# Qiao.net
KiCad netlist of a schematic drawn in Altium Designer
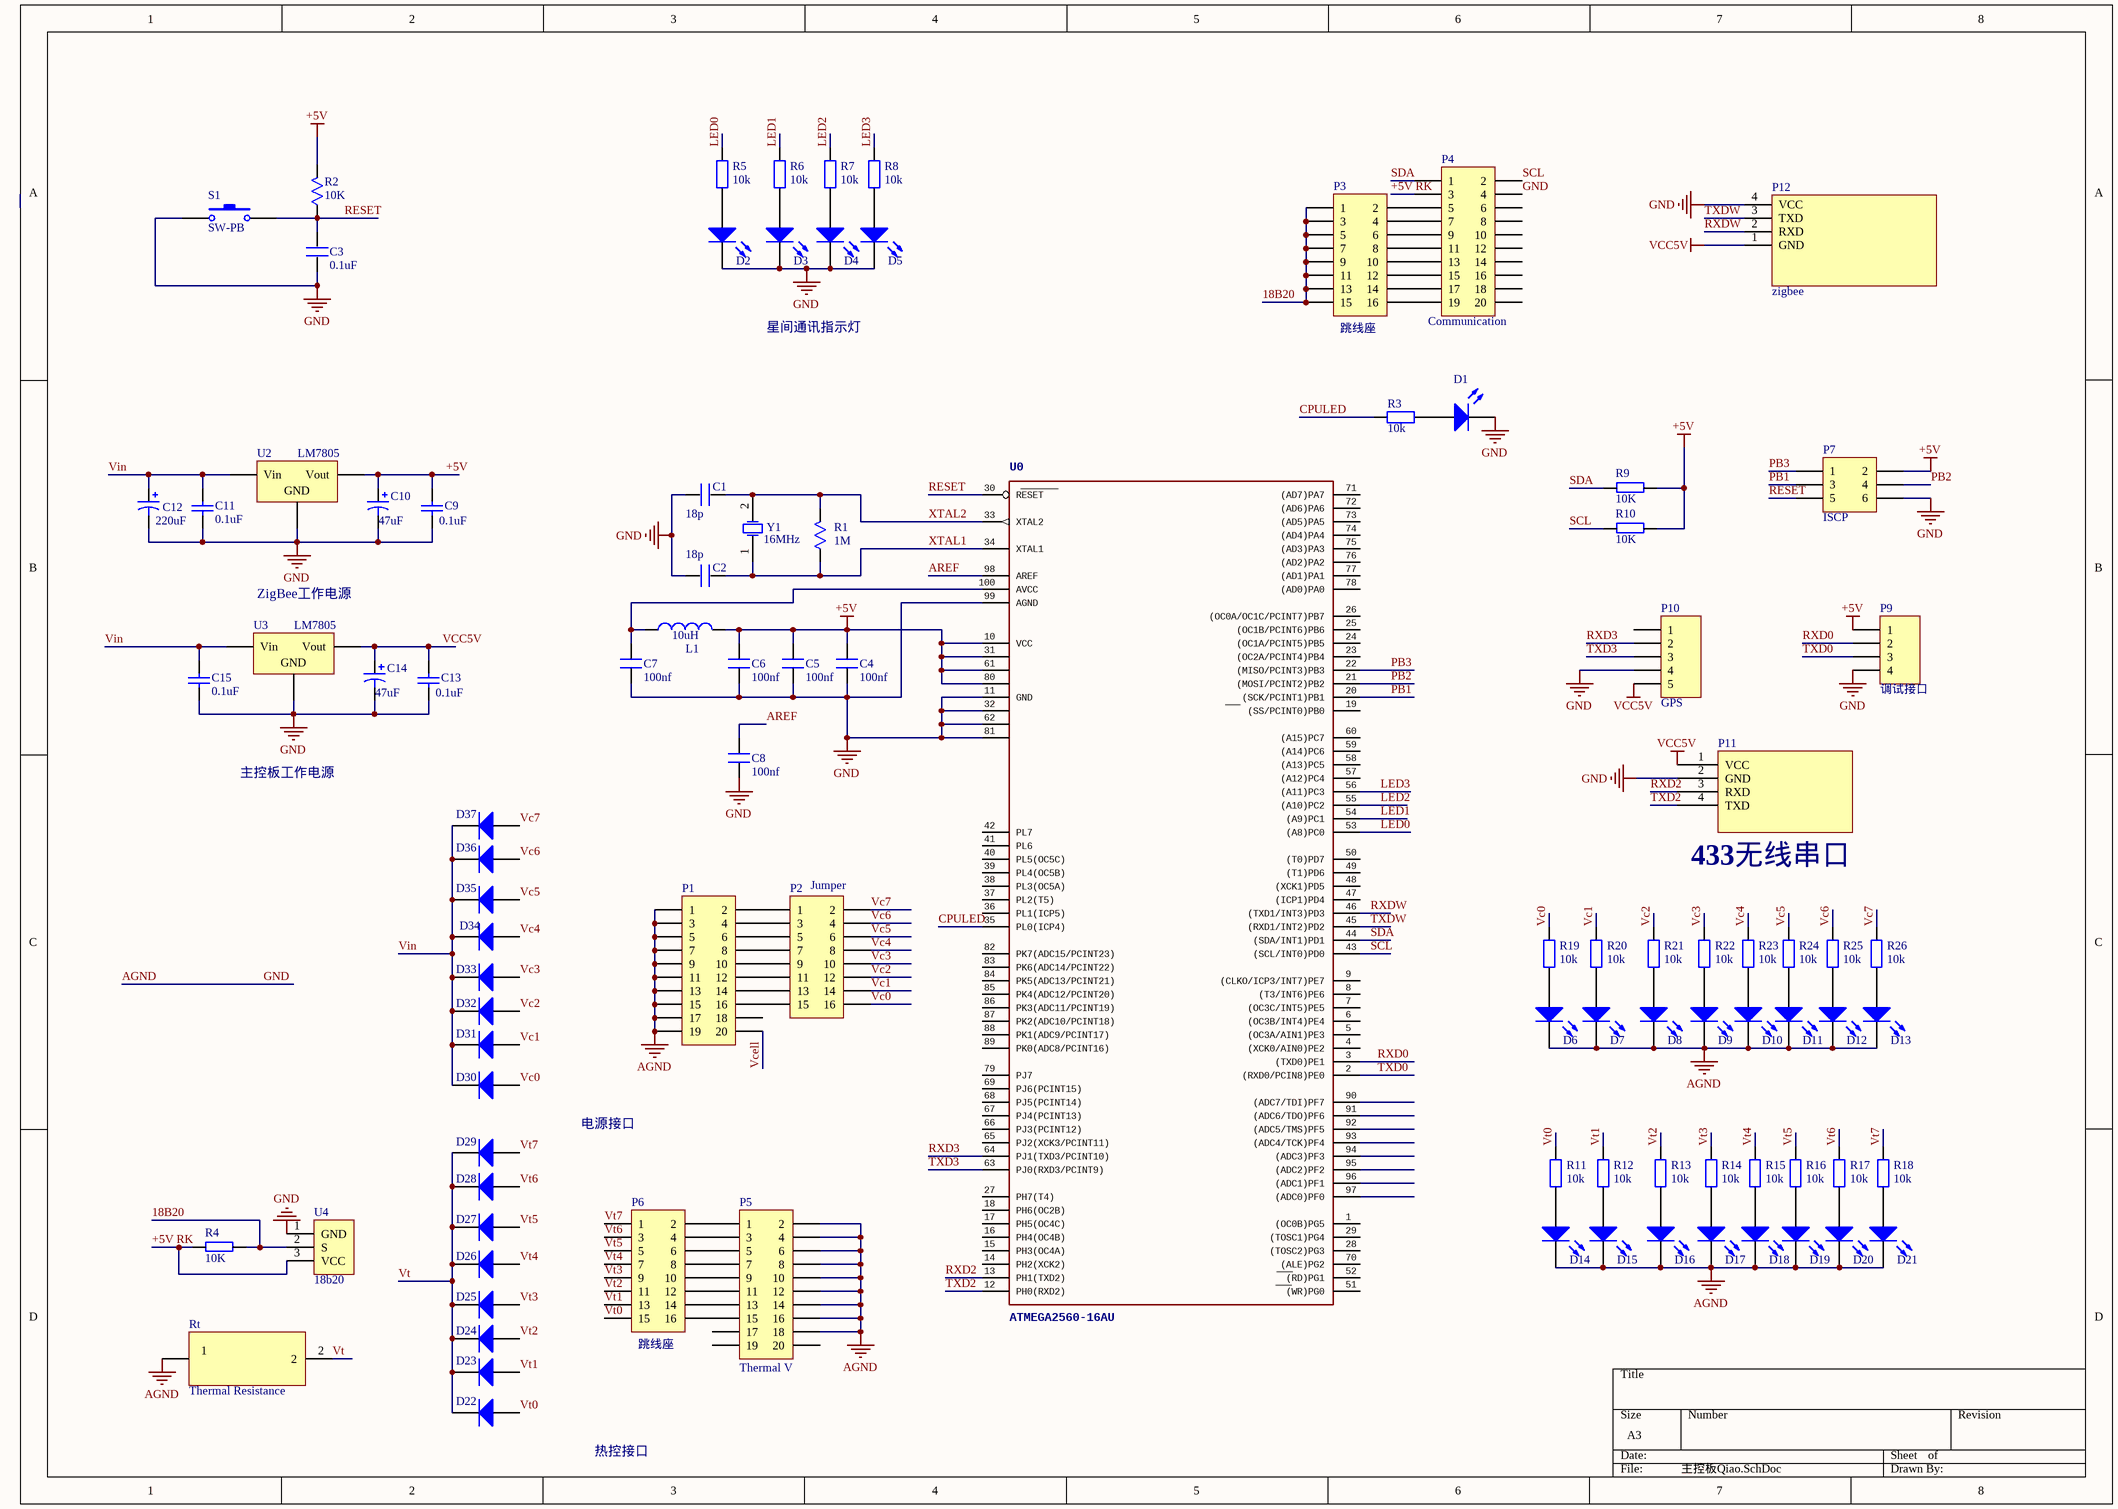
[diagram p0: 主控板Qiao.SchDoc]

(export (version "E")
  (design (tool "Eeschema 10.0.6"))
  (components
    (comp (ref "C1") (value "18p") (footprint "CAPC3216M") (libsource (lib "STM32封装库") (part "C_1")))
    (comp (ref "C2") (value "18p") (footprint "CAPC3216M") (libsource (lib "STM32封装库") (part "C_1")))
    (comp (ref "C3") (value "0.1uF") (footprint "CAPC3216M") (libsource (lib "STM32封装库") (part "C_3")))
    (comp (ref "C4") (value "100nf") (footprint "CAPC3216M") (libsource (lib "STM32封装库") (part "C")))
    (comp (ref "C5") (value "100nf") (footprint "CAPC3216M") (libsource (lib "STM32封装库") (part "C")))
    (comp (ref "C6") (value "100nf") (footprint "CAPC3216M") (libsource (lib "STM32封装库") (part "C")))
    (comp (ref "C7") (value "100nf") (footprint "CAPC3216M") (libsource (lib "STM32封装库") (part "C")))
    (comp (ref "C8") (value "100nf") (footprint "CAPC3216M") (libsource (lib "STM32封装库") (part "C")))
    (comp (ref "C9")
      (value "0.1uF")
      (footprint "CAPC3216M")
      (description "0.1uf")
      (fields (field (name "PUBLISHER") "Altium Limited"))
      (libsource (lib "Miscellaneous Devices") (part "Cap Semi"))
    )
    (comp (ref "C10")
      (value "47uF")
      (footprint "25V47uF")
      (description "10uf")
      (fields (field (name "Comment") "25V47uF") (field (name "PUBLISHER") "Altium Limited"))
      (libsource (lib "Miscellaneous Devices") (part "Cap Pol3"))
    )
    (comp (ref "C11")
      (value "0.1uF")
      (footprint "CAPC3216M")
      (description "0.1uf")
      (fields (field (name "PUBLISHER") "Altium Limited"))
      (libsource (lib "Miscellaneous Devices") (part "Cap"))
    )
    (comp (ref "C12")
      (value "220uF")
      (footprint "25V47uF")
      (description "10uf")
      (fields (field (name "Comment") "50V220uF") (field (name "PUBLISHER") "Altium Limited"))
      (libsource (lib "Miscellaneous Devices") (part "Cap Pol3"))
    )
    (comp (ref "C13")
      (value "0.1uF")
      (footprint "CAPC3216M")
      (description "0.1uf")
      (fields (field (name "PUBLISHER") "Altium Limited"))
      (libsource (lib "Miscellaneous Devices") (part "Cap Semi"))
    )
    (comp (ref "C14")
      (value "47uF")
      (footprint "25V47uF")
      (description "10uf")
      (fields (field (name "Comment") "25V47uF") (field (name "PUBLISHER") "Altium Limited"))
      (libsource (lib "Miscellaneous Devices") (part "Cap Pol3"))
    )
    (comp (ref "C15")
      (value "0.1uF")
      (footprint "CAPC3216M")
      (description "0.1uf")
      (fields (field (name "PUBLISHER") "Altium Limited"))
      (libsource (lib "Miscellaneous Devices") (part "Cap"))
    )
    (comp (ref "D1")
      (value "LED")
      (footprint "DIPLED")
      (description "Typical RED, GREEN, YELLOW, AMBER GaAs LED")
      (fields (field (name "PUBLISHER") "Altium Limited"))
      (libsource (lib "Miscellaneous Devices") (part "LED2"))
    )
    (comp (ref "D2")
      (value "LED")
      (footprint "LED")
      (description "Typical RED, GREEN, YELLOW, AMBER GaAs LED")
      (fields (field (name "PUBLISHER") "Altium Limited"))
      (libsource (lib "Miscellaneous Devices") (part "LED2"))
    )
    (comp (ref "D3")
      (value "LED")
      (footprint "LED")
      (description "Typical RED, GREEN, YELLOW, AMBER GaAs LED")
      (fields (field (name "PUBLISHER") "Altium Limited"))
      (libsource (lib "Miscellaneous Devices") (part "LED2"))
    )
    (comp (ref "D4")
      (value "LED")
      (footprint "LED")
      (description "Typical RED, GREEN, YELLOW, AMBER GaAs LED")
      (fields (field (name "PUBLISHER") "Altium Limited"))
      (libsource (lib "Miscellaneous Devices") (part "LED2"))
    )
    (comp (ref "D5")
      (value "LED")
      (footprint "LED")
      (description "Typical RED, GREEN, YELLOW, AMBER GaAs LED")
      (fields (field (name "PUBLISHER") "Altium Limited"))
      (libsource (lib "Miscellaneous Devices") (part "LED2"))
    )
    (comp (ref "D6")
      (value "LED")
      (footprint "LED")
      (description "Typical RED, GREEN, YELLOW, AMBER GaAs LED")
      (fields (field (name "PUBLISHER") "Altium Limited"))
      (libsource (lib "Miscellaneous Devices") (part "LED2"))
    )
    (comp (ref "D7")
      (value "LED")
      (footprint "LED")
      (description "Typical RED, GREEN, YELLOW, AMBER GaAs LED")
      (fields (field (name "PUBLISHER") "Altium Limited"))
      (libsource (lib "Miscellaneous Devices") (part "LED2"))
    )
    (comp (ref "D8")
      (value "LED")
      (footprint "LED")
      (description "Typical RED, GREEN, YELLOW, AMBER GaAs LED")
      (fields (field (name "PUBLISHER") "Altium Limited"))
      (libsource (lib "Miscellaneous Devices") (part "LED2"))
    )
    (comp (ref "D9")
      (value "LED")
      (footprint "LED")
      (description "Typical RED, GREEN, YELLOW, AMBER GaAs LED")
      (fields (field (name "PUBLISHER") "Altium Limited"))
      (libsource (lib "Miscellaneous Devices") (part "LED2"))
    )
    (comp (ref "D10")
      (value "LED")
      (footprint "LED")
      (description "Typical RED, GREEN, YELLOW, AMBER GaAs LED")
      (fields (field (name "PUBLISHER") "Altium Limited"))
      (libsource (lib "Miscellaneous Devices") (part "LED2"))
    )
    (comp (ref "D11")
      (value "LED")
      (footprint "LED")
      (description "Typical RED, GREEN, YELLOW, AMBER GaAs LED")
      (fields (field (name "PUBLISHER") "Altium Limited"))
      (libsource (lib "Miscellaneous Devices") (part "LED2"))
    )
    (comp (ref "D12")
      (value "LED")
      (footprint "LED")
      (description "Typical RED, GREEN, YELLOW, AMBER GaAs LED")
      (fields (field (name "PUBLISHER") "Altium Limited"))
      (libsource (lib "Miscellaneous Devices") (part "LED2"))
    )
    (comp (ref "D13")
      (value "LED")
      (footprint "LED")
      (description "Typical RED, GREEN, YELLOW, AMBER GaAs LED")
      (fields (field (name "PUBLISHER") "Altium Limited"))
      (libsource (lib "Miscellaneous Devices") (part "LED2"))
    )
    (comp (ref "D14")
      (value "LED")
      (footprint "LED")
      (description "Typical RED, GREEN, YELLOW, AMBER GaAs LED")
      (fields (field (name "PUBLISHER") "Altium Limited"))
      (libsource (lib "Miscellaneous Devices") (part "LED2"))
    )
    (comp (ref "D15")
      (value "LED")
      (footprint "LED")
      (description "Typical RED, GREEN, YELLOW, AMBER GaAs LED")
      (fields (field (name "PUBLISHER") "Altium Limited"))
      (libsource (lib "Miscellaneous Devices") (part "LED2"))
    )
    (comp (ref "D16")
      (value "LED")
      (footprint "LED")
      (description "Typical RED, GREEN, YELLOW, AMBER GaAs LED")
      (fields (field (name "PUBLISHER") "Altium Limited"))
      (libsource (lib "Miscellaneous Devices") (part "LED2"))
    )
    (comp (ref "D17")
      (value "LED")
      (footprint "LED")
      (description "Typical RED, GREEN, YELLOW, AMBER GaAs LED")
      (fields (field (name "PUBLISHER") "Altium Limited"))
      (libsource (lib "Miscellaneous Devices") (part "LED2"))
    )
    (comp (ref "D18")
      (value "LED")
      (footprint "LED")
      (description "Typical RED, GREEN, YELLOW, AMBER GaAs LED")
      (fields (field (name "PUBLISHER") "Altium Limited"))
      (libsource (lib "Miscellaneous Devices") (part "LED2"))
    )
    (comp (ref "D19")
      (value "LED")
      (footprint "LED")
      (description "Typical RED, GREEN, YELLOW, AMBER GaAs LED")
      (fields (field (name "PUBLISHER") "Altium Limited"))
      (libsource (lib "Miscellaneous Devices") (part "LED2"))
    )
    (comp (ref "D20")
      (value "LED")
      (footprint "LED")
      (description "Typical RED, GREEN, YELLOW, AMBER GaAs LED")
      (fields (field (name "PUBLISHER") "Altium Limited"))
      (libsource (lib "Miscellaneous Devices") (part "LED2"))
    )
    (comp (ref "D21")
      (value "LED")
      (footprint "LED")
      (description "Typical RED, GREEN, YELLOW, AMBER GaAs LED")
      (fields (field (name "PUBLISHER") "Altium Limited"))
      (libsource (lib "Miscellaneous Devices") (part "LED2"))
    )
    (comp (ref "D22")
      (value "1N4001")
      (footprint "SMB")
      (description "1 Amp General Purpose Rectifier")
      (fields (field (name "PUBLISHER") "Altium Limited"))
      (libsource (lib "Miscellaneous Devices") (part "Diode 1N4001"))
    )
    (comp (ref "D23")
      (value "1N4001")
      (footprint "SMB")
      (description "1 Amp General Purpose Rectifier")
      (fields (field (name "PUBLISHER") "Altium Limited"))
      (libsource (lib "Miscellaneous Devices") (part "Diode 1N4001"))
    )
    (comp (ref "D24")
      (value "1N4001")
      (footprint "SMB")
      (description "1 Amp General Purpose Rectifier")
      (fields (field (name "PUBLISHER") "Altium Limited"))
      (libsource (lib "Miscellaneous Devices") (part "Diode 1N4001"))
    )
    (comp (ref "D25")
      (value "1N4001")
      (footprint "SMB")
      (description "1 Amp General Purpose Rectifier")
      (fields (field (name "PUBLISHER") "Altium Limited"))
      (libsource (lib "Miscellaneous Devices") (part "Diode 1N4001"))
    )
    (comp (ref "D26")
      (value "1N4001")
      (footprint "SMB")
      (description "1 Amp General Purpose Rectifier")
      (fields (field (name "PUBLISHER") "Altium Limited"))
      (libsource (lib "Miscellaneous Devices") (part "Diode 1N4001"))
    )
    (comp (ref "D27")
      (value "1N4001")
      (footprint "SMB")
      (description "1 Amp General Purpose Rectifier")
      (fields (field (name "PUBLISHER") "Altium Limited"))
      (libsource (lib "Miscellaneous Devices") (part "Diode 1N4001"))
    )
    (comp (ref "D28")
      (value "1N4001")
      (footprint "SMB")
      (description "1 Amp General Purpose Rectifier")
      (fields (field (name "PUBLISHER") "Altium Limited"))
      (libsource (lib "Miscellaneous Devices") (part "Diode 1N4001"))
    )
    (comp (ref "D29")
      (value "1N4001")
      (footprint "SMB")
      (description "1 Amp General Purpose Rectifier")
      (fields (field (name "PUBLISHER") "Altium Limited"))
      (libsource (lib "Miscellaneous Devices") (part "Diode 1N4001"))
    )
    (comp (ref "D30")
      (value "1N4001")
      (footprint "SMB")
      (description "1 Amp General Purpose Rectifier")
      (fields (field (name "PUBLISHER") "Altium Limited"))
      (libsource (lib "Miscellaneous Devices") (part "Diode 1N4001"))
    )
    (comp (ref "D31")
      (value "1N4001")
      (footprint "SMB")
      (description "1 Amp General Purpose Rectifier")
      (fields (field (name "PUBLISHER") "Altium Limited"))
      (libsource (lib "Miscellaneous Devices") (part "Diode 1N4001"))
    )
    (comp (ref "D32")
      (value "1N4001")
      (footprint "SMB")
      (description "1 Amp General Purpose Rectifier")
      (fields (field (name "PUBLISHER") "Altium Limited"))
      (libsource (lib "Miscellaneous Devices") (part "Diode 1N4001"))
    )
    (comp (ref "D33")
      (value "1N4001")
      (footprint "SMB")
      (description "1 Amp General Purpose Rectifier")
      (fields (field (name "PUBLISHER") "Altium Limited"))
      (libsource (lib "Miscellaneous Devices") (part "Diode 1N4001"))
    )
    (comp (ref "D34")
      (value "1N4001")
      (footprint "SMB")
      (description "1 Amp General Purpose Rectifier")
      (fields (field (name "PUBLISHER") "Altium Limited"))
      (libsource (lib "Miscellaneous Devices") (part "Diode 1N4001"))
    )
    (comp (ref "D35")
      (value "1N4001")
      (footprint "SMB")
      (description "1 Amp General Purpose Rectifier")
      (fields (field (name "PUBLISHER") "Altium Limited"))
      (libsource (lib "Miscellaneous Devices") (part "Diode 1N4001"))
    )
    (comp (ref "D36")
      (value "1N4001")
      (footprint "SMB")
      (description "1 Amp General Purpose Rectifier")
      (fields (field (name "PUBLISHER") "Altium Limited"))
      (libsource (lib "Miscellaneous Devices") (part "Diode 1N4001"))
    )
    (comp (ref "D37")
      (value "1N4001")
      (footprint "SMB")
      (description "1 Amp General Purpose Rectifier")
      (fields (field (name "PUBLISHER") "Altium Limited"))
      (libsource (lib "Miscellaneous Devices") (part "Diode 1N4001"))
    )
    (comp (ref "L1")
      (value "10uH")
      (footprint "CAPC3216M")
      (description "Inductor")
      (fields (field (name "PUBLISHER") "Altium Limited"))
      (libsource (lib "Miscellaneous Devices") (part "Inductor"))
    )
    (comp (ref "P1")
      (value "Power Interface")
      (footprint "HDR2X10")
      (description "Header, 10-Pin, Dual row")
      (fields (field (name "PUBLISHER") "Altium Limited"))
      (libsource (lib "Miscellaneous Connectors") (part "Header 10X2"))
    )
    (comp (ref "P2")
      (value "Jumper")
      (footprint "HDR2X8")
      (description "Header, 8-Pin, Dual row")
      (fields (field (name "PUBLISHER") "Altium Limited"))
      (libsource (lib "Miscellaneous Connectors") (part "Header 8X2"))
    )
    (comp (ref "P3")
      (value "跳线座")
      (footprint "HDR2X8")
      (description "Header, 8-Pin, Dual row")
      (fields (field (name "PUBLISHER") "Altium Limited"))
      (libsource (lib "Miscellaneous Connectors") (part "Header 8X2"))
    )
    (comp (ref "P4")
      (value "Communication")
      (footprint "HDR2X10")
      (description "Header, 10-Pin, Dual row")
      (fields (field (name "PUBLISHER") "Altium Limited"))
      (libsource (lib "Miscellaneous Connectors") (part "Header 10X2"))
    )
    (comp (ref "P5")
      (value "Thermal V")
      (footprint "HDR2X10")
      (description "Header, 10-Pin, Dual row")
      (fields (field (name "PUBLISHER") "Altium Limited"))
      (libsource (lib "Miscellaneous Connectors") (part "Header 10X2"))
    )
    (comp (ref "P6")
      (value "跳线座")
      (footprint "HDR2X8")
      (description "Header, 8-Pin, Dual row")
      (fields (field (name "PUBLISHER") "Altium Limited"))
      (libsource (lib "Miscellaneous Connectors") (part "Header 8X2"))
    )
    (comp (ref "P7")
      (value "ISCP")
      (footprint "HDR2X3")
      (description "Header, 3-Pin, Dual row")
      (fields (field (name "PUBLISHER") "Altium Limited"))
      (libsource (lib "Miscellaneous Connectors") (part "Header 3X2"))
    )
    (comp (ref "P9")
      (value "调试接口")
      (footprint "HDR1X4")
      (description "Header, 4-Pin")
      (fields (field (name "PUBLISHER") "Altium Limited"))
      (libsource (lib "Miscellaneous Connectors") (part "Header 4"))
    )
    (comp (ref "P10")
      (value "GPS")
      (footprint "GPS")
      (description "Header, 5-Pin")
      (fields (field (name "PUBLISHER") "Altium Limited"))
      (libsource (lib "Miscellaneous Connectors") (part "Header 5"))
    )
    (comp (ref "P11") (value "433无线串口") (footprint "433PCB") (libsource (lib "433") (part "433无线串口")))
    (comp (ref "P12") (value "zigbee") (footprint "ZigBee") (libsource (lib "zigbee") (part "zigbee")))
    (comp (ref "R1") (value "1M") (footprint "RESC3216M") (libsource (lib "YT1_SCH_99SE") (part "RES")))
    (comp (ref "R2") (value "10K") (footprint "RESC3216M") (libsource (lib "YT1_SCH_99SE") (part "RES")))
    (comp (ref "R3")
      (value "10k")
      (footprint "RESC3216M")
      (description "5.1k")
      (fields (field (name "Comment") "10K") (field (name "PUBLISHER") "Altium Limited"))
      (libsource (lib "") (part "Res2_1"))
    )
    (comp (ref "R4") (value "10K") (footprint "RESC3216M") (libsource (lib "STM32封装库") (part "R")))
    (comp (ref "R5")
      (value "10k")
      (footprint "RESC3216M")
      (description "5.1k")
      (fields (field (name "Comment") "10K") (field (name "PUBLISHER") "Altium Limited"))
      (libsource (lib "Miscellaneous Devices") (part "Res2"))
    )
    (comp (ref "R6")
      (value "10k")
      (footprint "RESC3216M")
      (description "5.1k")
      (fields (field (name "Comment") "10K") (field (name "PUBLISHER") "Altium Limited"))
      (libsource (lib "Miscellaneous Devices") (part "Res2"))
    )
    (comp (ref "R7")
      (value "10k")
      (footprint "RESC3216M")
      (description "5.1k")
      (fields (field (name "Comment") "10K") (field (name "PUBLISHER") "Altium Limited"))
      (libsource (lib "Miscellaneous Devices") (part "Res2"))
    )
    (comp (ref "R8")
      (value "10k")
      (footprint "RESC3216M")
      (description "5.1k")
      (fields (field (name "Comment") "10K") (field (name "PUBLISHER") "Altium Limited"))
      (libsource (lib "Miscellaneous Devices") (part "Res2"))
    )
    (comp (ref "R9") (value "10K") (footprint "RESC3216M") (libsource (lib "STM32封装库") (part "R")))
    (comp (ref "R10") (value "10K") (footprint "RESC3216M") (libsource (lib "STM32封装库") (part "R")))
    (comp (ref "R11")
      (value "10k")
      (footprint "RESC3216M")
      (description "5.1k")
      (fields (field (name "Comment") "10K") (field (name "PUBLISHER") "Altium Limited"))
      (libsource (lib "Miscellaneous Devices") (part "Res2"))
    )
    (comp (ref "R12")
      (value "10k")
      (footprint "RESC3216M")
      (description "5.1k")
      (fields (field (name "Comment") "10K") (field (name "PUBLISHER") "Altium Limited"))
      (libsource (lib "Miscellaneous Devices") (part "Res2"))
    )
    (comp (ref "R13")
      (value "10k")
      (footprint "RESC3216M")
      (description "5.1k")
      (fields (field (name "Comment") "10K") (field (name "PUBLISHER") "Altium Limited"))
      (libsource (lib "Miscellaneous Devices") (part "Res2"))
    )
    (comp (ref "R14")
      (value "10k")
      (footprint "RESC3216M")
      (description "5.1k")
      (fields (field (name "Comment") "10K") (field (name "PUBLISHER") "Altium Limited"))
      (libsource (lib "Miscellaneous Devices") (part "Res2"))
    )
    (comp (ref "R15")
      (value "10k")
      (footprint "RESC3216M")
      (description "5.1k")
      (fields (field (name "Comment") "10K") (field (name "PUBLISHER") "Altium Limited"))
      (libsource (lib "Miscellaneous Devices") (part "Res2"))
    )
    (comp (ref "R16")
      (value "10k")
      (footprint "RESC3216M")
      (description "5.1k")
      (fields (field (name "Comment") "10K") (field (name "PUBLISHER") "Altium Limited"))
      (libsource (lib "Miscellaneous Devices") (part "Res2"))
    )
    (comp (ref "R17")
      (value "10k")
      (footprint "RESC3216M")
      (description "5.1k")
      (fields (field (name "Comment") "10K") (field (name "PUBLISHER") "Altium Limited"))
      (libsource (lib "Miscellaneous Devices") (part "Res2"))
    )
    (comp (ref "R18")
      (value "10k")
      (footprint "RESC3216M")
      (description "5.1k")
      (fields (field (name "Comment") "10K") (field (name "PUBLISHER") "Altium Limited"))
      (libsource (lib "Miscellaneous Devices") (part "Res2"))
    )
    (comp (ref "R19")
      (value "10k")
      (footprint "RESC3216M")
      (description "5.1k")
      (fields (field (name "Comment") "10K") (field (name "PUBLISHER") "Altium Limited"))
      (libsource (lib "Miscellaneous Devices") (part "Res2"))
    )
    (comp (ref "R20")
      (value "10k")
      (footprint "RESC3216M")
      (description "5.1k")
      (fields (field (name "Comment") "10K") (field (name "PUBLISHER") "Altium Limited"))
      (libsource (lib "Miscellaneous Devices") (part "Res2"))
    )
    (comp (ref "R21")
      (value "10k")
      (footprint "RESC3216M")
      (description "5.1k")
      (fields (field (name "Comment") "10K") (field (name "PUBLISHER") "Altium Limited"))
      (libsource (lib "Miscellaneous Devices") (part "Res2"))
    )
    (comp (ref "R22")
      (value "10k")
      (footprint "RESC3216M")
      (description "5.1k")
      (fields (field (name "Comment") "10K") (field (name "PUBLISHER") "Altium Limited"))
      (libsource (lib "Miscellaneous Devices") (part "Res2"))
    )
    (comp (ref "R23")
      (value "10k")
      (footprint "RESC3216M")
      (description "5.1k")
      (fields (field (name "Comment") "10K") (field (name "PUBLISHER") "Altium Limited"))
      (libsource (lib "Miscellaneous Devices") (part "Res2"))
    )
    (comp (ref "R24")
      (value "10k")
      (footprint "RESC3216M")
      (description "5.1k")
      (fields (field (name "Comment") "10K") (field (name "PUBLISHER") "Altium Limited"))
      (libsource (lib "Miscellaneous Devices") (part "Res2"))
    )
    (comp (ref "R25")
      (value "10k")
      (footprint "RESC3216M")
      (description "5.1k")
      (fields (field (name "Comment") "10K") (field (name "PUBLISHER") "Altium Limited"))
      (libsource (lib "Miscellaneous Devices") (part "Res2"))
    )
    (comp (ref "R26")
      (value "10k")
      (footprint "RESC3216M")
      (description "5.1k")
      (fields (field (name "Comment") "10K") (field (name "PUBLISHER") "Altium Limited"))
      (libsource (lib "Miscellaneous Devices") (part "Res2"))
    )
    (comp (ref "Rt")
      (value "Thermal Resistance")
      (footprint "Thermal Res")
      (libsource (lib "MyFootprintLibrary") (part "ThermalResistance"))
    )
    (comp (ref "S1")
      (value "SW-PB")
      (footprint "PUSH BUTTON 6x6")
      (description "Switch")
      (fields (field (name "PUBLISHER") "Altium Limited"))
      (libsource (lib "Miscellaneous Devices") (part "SW-PB"))
    )
    (comp (ref "U0")
      (value "ATMEGA2560-16AU")
      (footprint "TQFP100")
      (libsource (lib "Arduino_MEGA_2560-Rev3") (part "ATMEGA2560AU"))
    )
    (comp (ref "U2")
      (value "LM7805")
      (footprint "DPAK-3")
      (description "Voltage Regulator")
      (fields (field (name "PUBLISHER") "Altium Limited"))
      (libsource (lib "Miscellaneous Devices") (part "Volt Reg"))
    )
    (comp (ref "U3")
      (value "LM7805")
      (footprint "DPAK-3")
      (description "Voltage Regulator")
      (fields (field (name "PUBLISHER") "Altium Limited"))
      (libsource (lib "Miscellaneous Devices") (part "Volt Reg"))
    )
    (comp (ref "U4") (value "18b20") (footprint "TO92") (libsource (lib "常用元件库") (part "18b20")))
    (comp (ref "Y1")
      (value "16MHz")
      (footprint "XTAL_US")
      (description "Crystal Oscillator")
      (fields (field (name "PUBLISHER") "Altium Limited"))
      (libsource (lib "电源管理板") (part "XTAL"))
    )
  )
  (nets
    (net (code "1") (name "+5V") (class "Default")
      (node (ref "C10") (pin "1") (pinfunction "1_1") (pintype "passive"))
      (node (ref "C4") (pin "2") (pintype "passive"))
      (node (ref "C5") (pin "2") (pintype "passive"))
      (node (ref "C6") (pin "2") (pintype "passive"))
      (node (ref "C9") (pin "2") (pinfunction "2_2") (pintype "passive"))
      (node (ref "L1") (pin "2") (pinfunction "2_2") (pintype "passive"))
      (node (ref "P7") (pin "2") (pinfunction "2_2") (pintype "passive"))
      (node (ref "P9") (pin "1") (pinfunction "1_1") (pintype "passive"))
      (node (ref "R10") (pin "1") (pintype "passive"))
      (node (ref "R2") (pin "2") (pinfunction "2_2") (pintype "passive"))
      (node (ref "R9") (pin "1") (pintype "passive"))
      (node (ref "U0") (pin "10") (pinfunction "VCC_10") (pintype "power_in"))
      (node (ref "U0") (pin "31") (pinfunction "VCC1_31") (pintype "power_in"))
      (node (ref "U0") (pin "61") (pinfunction "VCC2_61") (pintype "power_in"))
      (node (ref "U0") (pin "80") (pinfunction "VCC3_80") (pintype "power_in"))
      (node (ref "U2") (pin "3") (pinfunction "Vout_3") (pintype "passive"))
    )
    (net (code "2") (name "/+5V RK") (class "Default")
      (node (ref "P4") (pin "3") (pinfunction "3_3") (pintype "passive"))
      (node (ref "R4") (pin "2") (pintype "passive"))
      (node (ref "U4") (pin "3") (pinfunction "VCC_3") (pintype "passive"))
    )
    (net (code "3") (name "/18B20") (class "Default")
      (node (ref "P3") (pin "1") (pinfunction "1_1") (pintype "passive"))
      (node (ref "P3") (pin "11") (pinfunction "11_11") (pintype "passive"))
      (node (ref "P3") (pin "13") (pinfunction "13_13") (pintype "passive"))
      (node (ref "P3") (pin "15") (pinfunction "15_15") (pintype "passive"))
      (node (ref "P3") (pin "3") (pinfunction "3_3") (pintype "passive"))
      (node (ref "P3") (pin "5") (pinfunction "5_5") (pintype "passive"))
      (node (ref "P3") (pin "7") (pinfunction "7_7") (pintype "passive"))
      (node (ref "P3") (pin "9") (pinfunction "9_9") (pintype "passive"))
      (node (ref "R4") (pin "1") (pintype "passive"))
      (node (ref "U4") (pin "2") (pinfunction "S_2") (pintype "passive"))
    )
    (net (code "4") (name "/AREF") (class "Default")
      (node (ref "C8") (pin "2") (pintype "passive"))
      (node (ref "U0") (pin "98") (pinfunction "AREF_98") (pintype "passive"))
    )
    (net (code "5") (name "/CPULED") (class "Default")
      (node (ref "R3") (pin "2") (pinfunction "2_2") (pintype "passive"))
      (node (ref "U0") (pin "35") (pinfunction "PL0(ICP4)_35") (pintype "passive"))
    )
    (net (code "6") (name "/LED0") (class "Default")
      (node (ref "R5") (pin "2") (pinfunction "2_2") (pintype "passive"))
      (node (ref "U0") (pin "53") (pinfunction "(A8)PC0_53") (pintype "passive"))
    )
    (net (code "7") (name "/LED1") (class "Default")
      (node (ref "R6") (pin "2") (pinfunction "2_2") (pintype "passive"))
      (node (ref "U0") (pin "54") (pinfunction "(A9)PC1_54") (pintype "passive"))
    )
    (net (code "8") (name "/LED2") (class "Default")
      (node (ref "R7") (pin "2") (pinfunction "2_2") (pintype "passive"))
      (node (ref "U0") (pin "55") (pinfunction "(A10)PC2_55") (pintype "passive"))
    )
    (net (code "9") (name "/LED3") (class "Default")
      (node (ref "R8") (pin "2") (pinfunction "2_2") (pintype "passive"))
      (node (ref "U0") (pin "56") (pinfunction "(A11)PC3_56") (pintype "passive"))
    )
    (net (code "10") (name "/PB1") (class "Default")
      (node (ref "P7") (pin "3") (pinfunction "3_3") (pintype "passive"))
      (node (ref "U0") (pin "20") (pinfunction "(SCK/PCINT1)PB1_20") (pintype "passive"))
    )
    (net (code "11") (name "/PB2") (class "Default")
      (node (ref "P7") (pin "4") (pinfunction "4_4") (pintype "passive"))
      (node (ref "U0") (pin "21") (pinfunction "(MOSI/PCINT2)PB2_21") (pintype "passive"))
    )
    (net (code "12") (name "/PB3") (class "Default")
      (node (ref "P7") (pin "1") (pinfunction "1_1") (pintype "passive"))
      (node (ref "U0") (pin "22") (pinfunction "(MISO/PCINT3)PB3_22") (pintype "passive"))
    )
    (net (code "13") (name "/RESET") (class "Default")
      (node (ref "C3") (pin "2") (pintype "passive"))
      (node (ref "P7") (pin "5") (pinfunction "5_5") (pintype "passive"))
      (node (ref "R2") (pin "1") (pinfunction "1_1") (pintype "passive"))
      (node (ref "S1") (pin "2") (pinfunction "2_2") (pintype "passive"))
      (node (ref "U0") (pin "30") (pinfunction "RESET_30") (pintype "passive"))
    )
    (net (code "14") (name "/RXD0") (class "Default")
      (node (ref "P9") (pin "2") (pinfunction "2_2") (pintype "passive"))
      (node (ref "U0") (pin "3") (pinfunction "(TXD0)PE1_3") (pintype "passive"))
    )
    (net (code "15") (name "/RXD2") (class "Default")
      (node (ref "P11") (pin "3") (pinfunction "RXD_3") (pintype "passive"))
      (node (ref "U0") (pin "13") (pinfunction "PH1(TXD2)_13") (pintype "passive"))
    )
    (net (code "16") (name "/RXD3") (class "Default")
      (node (ref "P10") (pin "2") (pinfunction "2_2") (pintype "passive"))
      (node (ref "U0") (pin "64") (pinfunction "PJ1(TXD3/PCINT10)_64") (pintype "passive"))
    )
    (net (code "17") (name "/RXDW") (class "Default")
      (node (ref "P12") (pin "2") (pinfunction "RXD_2") (pintype "passive"))
      (node (ref "U0") (pin "46") (pinfunction "(TXD1/INT3)PD3_46") (pintype "passive"))
    )
    (net (code "18") (name "/SCL") (class "Default")
      (node (ref "P4") (pin "2") (pinfunction "2_2") (pintype "passive"))
      (node (ref "R10") (pin "2") (pintype "passive"))
      (node (ref "U0") (pin "43") (pinfunction "(SCL/INT0)PD0_43") (pintype "passive"))
    )
    (net (code "19") (name "/SDA") (class "Default")
      (node (ref "P4") (pin "1") (pinfunction "1_1") (pintype "passive"))
      (node (ref "R9") (pin "2") (pintype "passive"))
      (node (ref "U0") (pin "44") (pinfunction "(SDA/INT1)PD1_44") (pintype "passive"))
    )
    (net (code "20") (name "/TXD0") (class "Default")
      (node (ref "P9") (pin "3") (pinfunction "3_3") (pintype "passive"))
      (node (ref "U0") (pin "2") (pinfunction "(RXD0/PCIN8)PE0_2") (pintype "passive"))
    )
    (net (code "21") (name "/TXD2") (class "Default")
      (node (ref "P11") (pin "4") (pinfunction "TXD_4") (pintype "passive"))
      (node (ref "U0") (pin "12") (pinfunction "PH0(RXD2)_12") (pintype "passive"))
    )
    (net (code "22") (name "/TXD3") (class "Default")
      (node (ref "P10") (pin "3") (pinfunction "3_3") (pintype "passive"))
      (node (ref "U0") (pin "63") (pinfunction "PJ0(RXD3/PCINT9)_63") (pintype "passive"))
    )
    (net (code "23") (name "/TXDW") (class "Default")
      (node (ref "P12") (pin "3") (pinfunction "TXD_3") (pintype "passive"))
      (node (ref "U0") (pin "45") (pinfunction "(RXD1/INT2)PD2_45") (pintype "passive"))
    )
    (net (code "24") (name "/Vc0") (class "Default")
      (node (ref "D30") (pin "1") (pinfunction "A_1") (pintype "passive"))
      (node (ref "P2") (pin "16") (pinfunction "16_16") (pintype "passive"))
      (node (ref "R19") (pin "2") (pinfunction "2_2") (pintype "passive"))
    )
    (net (code "25") (name "/Vc1") (class "Default")
      (node (ref "D31") (pin "1") (pinfunction "A_1") (pintype "passive"))
      (node (ref "P2") (pin "14") (pinfunction "14_14") (pintype "passive"))
      (node (ref "R20") (pin "2") (pinfunction "2_2") (pintype "passive"))
    )
    (net (code "26") (name "/Vc2") (class "Default")
      (node (ref "D32") (pin "1") (pinfunction "A_1") (pintype "passive"))
      (node (ref "P2") (pin "12") (pinfunction "12_12") (pintype "passive"))
      (node (ref "R21") (pin "2") (pinfunction "2_2") (pintype "passive"))
    )
    (net (code "27") (name "/Vc3") (class "Default")
      (node (ref "D33") (pin "1") (pinfunction "A_1") (pintype "passive"))
      (node (ref "P2") (pin "10") (pinfunction "10_10") (pintype "passive"))
      (node (ref "R22") (pin "2") (pinfunction "2_2") (pintype "passive"))
    )
    (net (code "28") (name "/Vc4") (class "Default")
      (node (ref "D34") (pin "1") (pinfunction "A_1") (pintype "passive"))
      (node (ref "P2") (pin "8") (pinfunction "8_8") (pintype "passive"))
      (node (ref "R23") (pin "2") (pinfunction "2_2") (pintype "passive"))
    )
    (net (code "29") (name "/Vc5") (class "Default")
      (node (ref "D35") (pin "1") (pinfunction "A_1") (pintype "passive"))
      (node (ref "P2") (pin "6") (pinfunction "6_6") (pintype "passive"))
      (node (ref "R24") (pin "2") (pinfunction "2_2") (pintype "passive"))
    )
    (net (code "30") (name "/Vc6") (class "Default")
      (node (ref "D36") (pin "1") (pinfunction "A_1") (pintype "passive"))
      (node (ref "P2") (pin "4") (pinfunction "4_4") (pintype "passive"))
      (node (ref "R25") (pin "2") (pinfunction "2_2") (pintype "passive"))
    )
    (net (code "31") (name "/Vc7") (class "Default")
      (node (ref "D37") (pin "1") (pinfunction "A_1") (pintype "passive"))
      (node (ref "P2") (pin "2") (pinfunction "2_2") (pintype "passive"))
      (node (ref "R26") (pin "2") (pinfunction "2_2") (pintype "passive"))
    )
    (net (code "32") (name "/Vcell") (class "Default")
      (node (ref "P1") (pin "20") (pinfunction "20_20") (pintype "passive"))
    )
    (net (code "33") (name "/Vin") (class "Default")
      (node (ref "C11") (pin "2") (pinfunction "2_2") (pintype "passive"))
      (node (ref "C12") (pin "1") (pinfunction "1_1") (pintype "passive"))
      (node (ref "C15") (pin "2") (pinfunction "2_2") (pintype "passive"))
      (node (ref "D30") (pin "2") (pinfunction "K_2") (pintype "passive"))
      (node (ref "D31") (pin "2") (pinfunction "K_2") (pintype "passive"))
      (node (ref "D32") (pin "2") (pinfunction "K_2") (pintype "passive"))
      (node (ref "D33") (pin "2") (pinfunction "K_2") (pintype "passive"))
      (node (ref "D34") (pin "2") (pinfunction "K_2") (pintype "passive"))
      (node (ref "D35") (pin "2") (pinfunction "K_2") (pintype "passive"))
      (node (ref "D36") (pin "2") (pinfunction "K_2") (pintype "passive"))
      (node (ref "D37") (pin "2") (pinfunction "K_2") (pintype "passive"))
      (node (ref "U2") (pin "1") (pinfunction "Vin_1") (pintype "passive"))
      (node (ref "U3") (pin "1") (pinfunction "Vin_1") (pintype "passive"))
    )
    (net (code "34") (name "/Vt") (class "Default")
      (node (ref "D22") (pin "2") (pinfunction "K_2") (pintype "passive"))
      (node (ref "D23") (pin "2") (pinfunction "K_2") (pintype "passive"))
      (node (ref "D24") (pin "2") (pinfunction "K_2") (pintype "passive"))
      (node (ref "D25") (pin "2") (pinfunction "K_2") (pintype "passive"))
      (node (ref "D26") (pin "2") (pinfunction "K_2") (pintype "passive"))
      (node (ref "D27") (pin "2") (pinfunction "K_2") (pintype "passive"))
      (node (ref "D28") (pin "2") (pinfunction "K_2") (pintype "passive"))
      (node (ref "D29") (pin "2") (pinfunction "K_2") (pintype "passive"))
      (node (ref "Rt") (pin "2") (pinfunction "2_2") (pintype "passive"))
    )
    (net (code "35") (name "/Vt0") (class "Default")
      (node (ref "D22") (pin "1") (pinfunction "A_1") (pintype "passive"))
      (node (ref "P6") (pin "15") (pinfunction "15_15") (pintype "passive"))
      (node (ref "R11") (pin "2") (pinfunction "2_2") (pintype "passive"))
    )
    (net (code "36") (name "/Vt1") (class "Default")
      (node (ref "D23") (pin "1") (pinfunction "A_1") (pintype "passive"))
      (node (ref "P6") (pin "13") (pinfunction "13_13") (pintype "passive"))
      (node (ref "R12") (pin "2") (pinfunction "2_2") (pintype "passive"))
    )
    (net (code "37") (name "/Vt2") (class "Default")
      (node (ref "D24") (pin "1") (pinfunction "A_1") (pintype "passive"))
      (node (ref "P6") (pin "11") (pinfunction "11_11") (pintype "passive"))
      (node (ref "R13") (pin "2") (pinfunction "2_2") (pintype "passive"))
    )
    (net (code "38") (name "/Vt3") (class "Default")
      (node (ref "D25") (pin "1") (pinfunction "A_1") (pintype "passive"))
      (node (ref "P6") (pin "9") (pinfunction "9_9") (pintype "passive"))
      (node (ref "R14") (pin "2") (pinfunction "2_2") (pintype "passive"))
    )
    (net (code "39") (name "/Vt4") (class "Default")
      (node (ref "D26") (pin "1") (pinfunction "A_1") (pintype "passive"))
      (node (ref "P6") (pin "7") (pinfunction "7_7") (pintype "passive"))
      (node (ref "R15") (pin "2") (pinfunction "2_2") (pintype "passive"))
    )
    (net (code "40") (name "/Vt5") (class "Default")
      (node (ref "D27") (pin "1") (pinfunction "A_1") (pintype "passive"))
      (node (ref "P6") (pin "5") (pinfunction "5_5") (pintype "passive"))
      (node (ref "R16") (pin "2") (pinfunction "2_2") (pintype "passive"))
    )
    (net (code "41") (name "/Vt6") (class "Default")
      (node (ref "D28") (pin "1") (pinfunction "A_1") (pintype "passive"))
      (node (ref "P6") (pin "3") (pinfunction "3_3") (pintype "passive"))
      (node (ref "R17") (pin "2") (pinfunction "2_2") (pintype "passive"))
    )
    (net (code "42") (name "/Vt7") (class "Default")
      (node (ref "D29") (pin "1") (pinfunction "A_1") (pintype "passive"))
      (node (ref "P6") (pin "1") (pinfunction "1_1") (pintype "passive"))
      (node (ref "R18") (pin "2") (pinfunction "2_2") (pintype "passive"))
    )
    (net (code "43") (name "/XTAL1") (class "Default")
      (node (ref "C2") (pin "2") (pintype "passive"))
      (node (ref "R1") (pin "1") (pinfunction "1_1") (pintype "passive"))
      (node (ref "U0") (pin "34") (pinfunction "XTAL1_34") (pintype "passive"))
      (node (ref "Y1") (pin "1") (pinfunction "OSC1_1") (pintype "passive"))
    )
    (net (code "44") (name "/XTAL2") (class "Default")
      (node (ref "C1") (pin "2") (pintype "passive"))
      (node (ref "R1") (pin "2") (pinfunction "2_2") (pintype "passive"))
      (node (ref "U0") (pin "33") (pinfunction "XTAL2_33") (pintype "output"))
      (node (ref "Y1") (pin "2") (pinfunction "OSC2_2") (pintype "passive"))
    )
    (net (code "45") (name "AGND") (class "Default")
      (node (ref "C1") (pin "1") (pintype "passive"))
      (node (ref "C10") (pin "2") (pinfunction "2_2") (pintype "passive"))
      (node (ref "C11") (pin "1") (pinfunction "1_1") (pintype "passive"))
      (node (ref "C12") (pin "2") (pinfunction "2_2") (pintype "passive"))
      (node (ref "C13") (pin "1") (pinfunction "1_1") (pintype "passive"))
      (node (ref "C14") (pin "2") (pinfunction "2_2") (pintype "passive"))
      (node (ref "C15") (pin "1") (pinfunction "1_1") (pintype "passive"))
      (node (ref "C2") (pin "1") (pintype "passive"))
      (node (ref "C3") (pin "1") (pintype "passive"))
      (node (ref "C4") (pin "1") (pintype "passive"))
      (node (ref "C5") (pin "1") (pintype "passive"))
      (node (ref "C6") (pin "1") (pintype "passive"))
      (node (ref "C7") (pin "1") (pintype "passive"))
      (node (ref "C8") (pin "1") (pintype "passive"))
      (node (ref "C9") (pin "1") (pinfunction "1_1") (pintype "passive"))
      (node (ref "D1") (pin "2") (pinfunction "K_2") (pintype "passive"))
      (node (ref "D10") (pin "2") (pinfunction "K_2") (pintype "passive"))
      (node (ref "D11") (pin "2") (pinfunction "K_2") (pintype "passive"))
      (node (ref "D12") (pin "2") (pinfunction "K_2") (pintype "passive"))
      (node (ref "D13") (pin "2") (pinfunction "K_2") (pintype "passive"))
      (node (ref "D14") (pin "2") (pinfunction "K_2") (pintype "passive"))
      (node (ref "D15") (pin "2") (pinfunction "K_2") (pintype "passive"))
      (node (ref "D16") (pin "2") (pinfunction "K_2") (pintype "passive"))
      (node (ref "D17") (pin "2") (pinfunction "K_2") (pintype "passive"))
      (node (ref "D18") (pin "2") (pinfunction "K_2") (pintype "passive"))
      (node (ref "D19") (pin "2") (pinfunction "K_2") (pintype "passive"))
      (node (ref "D2") (pin "2") (pinfunction "K_2") (pintype "passive"))
      (node (ref "D20") (pin "2") (pinfunction "K_2") (pintype "passive"))
      (node (ref "D21") (pin "2") (pinfunction "K_2") (pintype "passive"))
      (node (ref "D3") (pin "2") (pinfunction "K_2") (pintype "passive"))
      (node (ref "D4") (pin "2") (pinfunction "K_2") (pintype "passive"))
      (node (ref "D5") (pin "2") (pinfunction "K_2") (pintype "passive"))
      (node (ref "D6") (pin "2") (pinfunction "K_2") (pintype "passive"))
      (node (ref "D7") (pin "2") (pinfunction "K_2") (pintype "passive"))
      (node (ref "D8") (pin "2") (pinfunction "K_2") (pintype "passive"))
      (node (ref "D9") (pin "2") (pinfunction "K_2") (pintype "passive"))
      (node (ref "P1") (pin "1") (pinfunction "1_1") (pintype "passive"))
      (node (ref "P1") (pin "11") (pinfunction "11_11") (pintype "passive"))
      (node (ref "P1") (pin "13") (pinfunction "13_13") (pintype "passive"))
      (node (ref "P1") (pin "15") (pinfunction "15_15") (pintype "passive"))
      (node (ref "P1") (pin "17") (pinfunction "17_17") (pintype "passive"))
      (node (ref "P1") (pin "19") (pinfunction "19_19") (pintype "passive"))
      (node (ref "P1") (pin "3") (pinfunction "3_3") (pintype "passive"))
      (node (ref "P1") (pin "5") (pinfunction "5_5") (pintype "passive"))
      (node (ref "P1") (pin "7") (pinfunction "7_7") (pintype "passive"))
      (node (ref "P1") (pin "9") (pinfunction "9_9") (pintype "passive"))
      (node (ref "P10") (pin "4") (pinfunction "4_4") (pintype "passive"))
      (node (ref "P11") (pin "2") (pinfunction "GND_2") (pintype "passive"))
      (node (ref "P12") (pin "4") (pinfunction "VCC_4") (pintype "passive"))
      (node (ref "P4") (pin "4") (pinfunction "4_4") (pintype "passive"))
      (node (ref "P5") (pin "10") (pinfunction "10_10") (pintype "passive"))
      (node (ref "P5") (pin "12") (pinfunction "12_12") (pintype "passive"))
      (node (ref "P5") (pin "14") (pinfunction "14_14") (pintype "passive"))
      (node (ref "P5") (pin "16") (pinfunction "16_16") (pintype "passive"))
      (node (ref "P5") (pin "18") (pinfunction "18_18") (pintype "passive"))
      (node (ref "P5") (pin "2") (pinfunction "2_2") (pintype "passive"))
      (node (ref "P5") (pin "4") (pinfunction "4_4") (pintype "passive"))
      (node (ref "P5") (pin "6") (pinfunction "6_6") (pintype "passive"))
      (node (ref "P5") (pin "8") (pinfunction "8_8") (pintype "passive"))
      (node (ref "P7") (pin "6") (pinfunction "6_6") (pintype "passive"))
      (node (ref "P9") (pin "4") (pinfunction "4_4") (pintype "passive"))
      (node (ref "Rt") (pin "1") (pinfunction "1_1") (pintype "passive"))
      (node (ref "S1") (pin "1") (pinfunction "1_1") (pintype "passive"))
      (node (ref "U0") (pin "11") (pinfunction "GND_11") (pintype "power_in"))
      (node (ref "U0") (pin "32") (pinfunction "GND1_32") (pintype "power_in"))
      (node (ref "U0") (pin "62") (pinfunction "GND2_62") (pintype "power_in"))
      (node (ref "U0") (pin "81") (pinfunction "GND3_81") (pintype "power_in"))
      (node (ref "U0") (pin "99") (pinfunction "AGND_99") (pintype "power_in"))
      (node (ref "U2") (pin "2") (pinfunction "GND_2") (pintype "passive"))
      (node (ref "U3") (pin "2") (pinfunction "GND_2") (pintype "passive"))
      (node (ref "U4") (pin "1") (pinfunction "GND_1") (pintype "passive"))
    )
    (net (code "46") (name "Net-(D1-A)") (class "Default")
      (node (ref "D1") (pin "1") (pinfunction "A_1") (pintype "passive"))
      (node (ref "R3") (pin "1") (pinfunction "1_1") (pintype "passive"))
    )
    (net (code "47") (name "Net-(D2-A)") (class "Default")
      (node (ref "D2") (pin "1") (pinfunction "A_1") (pintype "passive"))
      (node (ref "R5") (pin "1") (pinfunction "1_1") (pintype "passive"))
    )
    (net (code "48") (name "Net-(D3-A)") (class "Default")
      (node (ref "D3") (pin "1") (pinfunction "A_1") (pintype "passive"))
      (node (ref "R6") (pin "1") (pinfunction "1_1") (pintype "passive"))
    )
    (net (code "49") (name "Net-(D4-A)") (class "Default")
      (node (ref "D4") (pin "1") (pinfunction "A_1") (pintype "passive"))
      (node (ref "R7") (pin "1") (pinfunction "1_1") (pintype "passive"))
    )
    (net (code "50") (name "Net-(D5-A)") (class "Default")
      (node (ref "D5") (pin "1") (pinfunction "A_1") (pintype "passive"))
      (node (ref "R8") (pin "1") (pinfunction "1_1") (pintype "passive"))
    )
    (net (code "51") (name "Net-(D6-A)") (class "Default")
      (node (ref "D6") (pin "1") (pinfunction "A_1") (pintype "passive"))
      (node (ref "R19") (pin "1") (pinfunction "1_1") (pintype "passive"))
    )
    (net (code "52") (name "Net-(D7-A)") (class "Default")
      (node (ref "D7") (pin "1") (pinfunction "A_1") (pintype "passive"))
      (node (ref "R20") (pin "1") (pinfunction "1_1") (pintype "passive"))
    )
    (net (code "53") (name "Net-(D8-A)") (class "Default")
      (node (ref "D8") (pin "1") (pinfunction "A_1") (pintype "passive"))
      (node (ref "R21") (pin "1") (pinfunction "1_1") (pintype "passive"))
    )
    (net (code "54") (name "Net-(D9-A)") (class "Default")
      (node (ref "D9") (pin "1") (pinfunction "A_1") (pintype "passive"))
      (node (ref "R22") (pin "1") (pinfunction "1_1") (pintype "passive"))
    )
    (net (code "55") (name "Net-(D10-A)") (class "Default")
      (node (ref "D10") (pin "1") (pinfunction "A_1") (pintype "passive"))
      (node (ref "R23") (pin "1") (pinfunction "1_1") (pintype "passive"))
    )
    (net (code "56") (name "Net-(D11-A)") (class "Default")
      (node (ref "D11") (pin "1") (pinfunction "A_1") (pintype "passive"))
      (node (ref "R24") (pin "1") (pinfunction "1_1") (pintype "passive"))
    )
    (net (code "57") (name "Net-(D12-A)") (class "Default")
      (node (ref "D12") (pin "1") (pinfunction "A_1") (pintype "passive"))
      (node (ref "R25") (pin "1") (pinfunction "1_1") (pintype "passive"))
    )
    (net (code "58") (name "Net-(D13-A)") (class "Default")
      (node (ref "D13") (pin "1") (pinfunction "A_1") (pintype "passive"))
      (node (ref "R26") (pin "1") (pinfunction "1_1") (pintype "passive"))
    )
    (net (code "59") (name "Net-(D14-A)") (class "Default")
      (node (ref "D14") (pin "1") (pinfunction "A_1") (pintype "passive"))
      (node (ref "R11") (pin "1") (pinfunction "1_1") (pintype "passive"))
    )
    (net (code "60") (name "Net-(D15-A)") (class "Default")
      (node (ref "D15") (pin "1") (pinfunction "A_1") (pintype "passive"))
      (node (ref "R12") (pin "1") (pinfunction "1_1") (pintype "passive"))
    )
    (net (code "61") (name "Net-(D16-A)") (class "Default")
      (node (ref "D16") (pin "1") (pinfunction "A_1") (pintype "passive"))
      (node (ref "R13") (pin "1") (pinfunction "1_1") (pintype "passive"))
    )
    (net (code "62") (name "Net-(D17-A)") (class "Default")
      (node (ref "D17") (pin "1") (pinfunction "A_1") (pintype "passive"))
      (node (ref "R14") (pin "1") (pinfunction "1_1") (pintype "passive"))
    )
    (net (code "63") (name "Net-(D18-A)") (class "Default")
      (node (ref "D18") (pin "1") (pinfunction "A_1") (pintype "passive"))
      (node (ref "R15") (pin "1") (pinfunction "1_1") (pintype "passive"))
    )
    (net (code "64") (name "Net-(D19-A)") (class "Default")
      (node (ref "D19") (pin "1") (pinfunction "A_1") (pintype "passive"))
      (node (ref "R16") (pin "1") (pinfunction "1_1") (pintype "passive"))
    )
    (net (code "65") (name "Net-(D20-A)") (class "Default")
      (node (ref "D20") (pin "1") (pinfunction "A_1") (pintype "passive"))
      (node (ref "R17") (pin "1") (pinfunction "1_1") (pintype "passive"))
    )
    (net (code "66") (name "Net-(D21-A)") (class "Default")
      (node (ref "D21") (pin "1") (pinfunction "A_1") (pintype "passive"))
      (node (ref "R18") (pin "1") (pinfunction "1_1") (pintype "passive"))
    )
    (net (code "67") (name "Net-(P1-Pad2)") (class "Default")
      (node (ref "P1") (pin "2") (pinfunction "2_2") (pintype "passive"))
      (node (ref "P2") (pin "1") (pinfunction "1_1") (pintype "passive"))
    )
    (net (code "68") (name "Net-(P1-Pad4)") (class "Default")
      (node (ref "P1") (pin "4") (pinfunction "4_4") (pintype "passive"))
      (node (ref "P2") (pin "3") (pinfunction "3_3") (pintype "passive"))
    )
    (net (code "69") (name "Net-(P1-Pad6)") (class "Default")
      (node (ref "P1") (pin "6") (pinfunction "6_6") (pintype "passive"))
      (node (ref "P2") (pin "5") (pinfunction "5_5") (pintype "passive"))
    )
    (net (code "70") (name "Net-(P1-Pad8)") (class "Default")
      (node (ref "P1") (pin "8") (pinfunction "8_8") (pintype "passive"))
      (node (ref "P2") (pin "7") (pinfunction "7_7") (pintype "passive"))
    )
    (net (code "71") (name "Net-(P1-Pad10)") (class "Default")
      (node (ref "P1") (pin "10") (pinfunction "10_10") (pintype "passive"))
      (node (ref "P2") (pin "9") (pinfunction "9_9") (pintype "passive"))
    )
    (net (code "72") (name "Net-(P1-Pad12)") (class "Default")
      (node (ref "P1") (pin "12") (pinfunction "12_12") (pintype "passive"))
      (node (ref "P2") (pin "11") (pinfunction "11_11") (pintype "passive"))
    )
    (net (code "73") (name "Net-(P1-Pad14)") (class "Default")
      (node (ref "P1") (pin "14") (pinfunction "14_14") (pintype "passive"))
      (node (ref "P2") (pin "13") (pinfunction "13_13") (pintype "passive"))
    )
    (net (code "74") (name "Net-(P1-Pad16)") (class "Default")
      (node (ref "P1") (pin "16") (pinfunction "16_16") (pintype "passive"))
      (node (ref "P2") (pin "15") (pinfunction "15_15") (pintype "passive"))
    )
    (net (code "75") (name "Net-(P3-Pad2)") (class "Default")
      (node (ref "P3") (pin "2") (pinfunction "2_2") (pintype "passive"))
      (node (ref "P4") (pin "5") (pinfunction "5_5") (pintype "passive"))
    )
    (net (code "76") (name "Net-(P3-Pad4)") (class "Default")
      (node (ref "P3") (pin "4") (pinfunction "4_4") (pintype "passive"))
      (node (ref "P4") (pin "7") (pinfunction "7_7") (pintype "passive"))
    )
    (net (code "77") (name "Net-(P3-Pad6)") (class "Default")
      (node (ref "P3") (pin "6") (pinfunction "6_6") (pintype "passive"))
      (node (ref "P4") (pin "9") (pinfunction "9_9") (pintype "passive"))
    )
    (net (code "78") (name "Net-(P3-Pad8)") (class "Default")
      (node (ref "P3") (pin "8") (pinfunction "8_8") (pintype "passive"))
      (node (ref "P4") (pin "11") (pinfunction "11_11") (pintype "passive"))
    )
    (net (code "79") (name "Net-(P3-Pad10)") (class "Default")
      (node (ref "P3") (pin "10") (pinfunction "10_10") (pintype "passive"))
      (node (ref "P4") (pin "13") (pinfunction "13_13") (pintype "passive"))
    )
    (net (code "80") (name "Net-(P3-Pad12)") (class "Default")
      (node (ref "P3") (pin "12") (pinfunction "12_12") (pintype "passive"))
      (node (ref "P4") (pin "15") (pinfunction "15_15") (pintype "passive"))
    )
    (net (code "81") (name "Net-(P3-Pad14)") (class "Default")
      (node (ref "P3") (pin "14") (pinfunction "14_14") (pintype "passive"))
      (node (ref "P4") (pin "17") (pinfunction "17_17") (pintype "passive"))
    )
    (net (code "82") (name "Net-(P3-Pad16)") (class "Default")
      (node (ref "P3") (pin "16") (pinfunction "16_16") (pintype "passive"))
      (node (ref "P4") (pin "19") (pinfunction "19_19") (pintype "passive"))
    )
    (net (code "83") (name "Net-(P5-Pad1)") (class "Default")
      (node (ref "P5") (pin "1") (pinfunction "1_1") (pintype "passive"))
      (node (ref "P6") (pin "2") (pinfunction "2_2") (pintype "passive"))
    )
    (net (code "84") (name "Net-(P5-Pad3)") (class "Default")
      (node (ref "P5") (pin "3") (pinfunction "3_3") (pintype "passive"))
      (node (ref "P6") (pin "4") (pinfunction "4_4") (pintype "passive"))
    )
    (net (code "85") (name "Net-(P5-Pad5)") (class "Default")
      (node (ref "P5") (pin "5") (pinfunction "5_5") (pintype "passive"))
      (node (ref "P6") (pin "6") (pinfunction "6_6") (pintype "passive"))
    )
    (net (code "86") (name "Net-(P5-Pad7)") (class "Default")
      (node (ref "P5") (pin "7") (pinfunction "7_7") (pintype "passive"))
      (node (ref "P6") (pin "8") (pinfunction "8_8") (pintype "passive"))
    )
    (net (code "87") (name "Net-(P5-Pad9)") (class "Default")
      (node (ref "P5") (pin "9") (pinfunction "9_9") (pintype "passive"))
      (node (ref "P6") (pin "10") (pinfunction "10_10") (pintype "passive"))
    )
    (net (code "88") (name "Net-(P5-Pad11)") (class "Default")
      (node (ref "P5") (pin "11") (pinfunction "11_11") (pintype "passive"))
      (node (ref "P6") (pin "12") (pinfunction "12_12") (pintype "passive"))
    )
    (net (code "89") (name "Net-(P5-Pad13)") (class "Default")
      (node (ref "P5") (pin "13") (pinfunction "13_13") (pintype "passive"))
      (node (ref "P6") (pin "14") (pinfunction "14_14") (pintype "passive"))
    )
    (net (code "90") (name "Net-(P5-Pad15)") (class "Default")
      (node (ref "P5") (pin "15") (pinfunction "15_15") (pintype "passive"))
      (node (ref "P6") (pin "16") (pinfunction "16_16") (pintype "passive"))
    )
    (net (code "91") (name "Net-(U0-AVCC)") (class "Default")
      (node (ref "C7") (pin "2") (pintype "passive"))
      (node (ref "L1") (pin "1") (pinfunction "1_1") (pintype "passive"))
      (node (ref "U0") (pin "100") (pinfunction "AVCC_100") (pintype "power_in"))
    )
    (net (code "92") (name "VCC5V") (class "Default")
      (node (ref "C13") (pin "2") (pinfunction "2_2") (pintype "passive"))
      (node (ref "C14") (pin "1") (pinfunction "1_1") (pintype "passive"))
      (node (ref "P10") (pin "5") (pinfunction "5_5") (pintype "passive"))
      (node (ref "P11") (pin "1") (pinfunction "VCC_1") (pintype "passive"))
      (node (ref "P12") (pin "1") (pinfunction "GND_1") (pintype "passive"))
      (node (ref "U3") (pin "3") (pinfunction "Vout_3") (pintype "passive"))
    )
    (net (code "93") (name "unconnected-(P1-Pad18)") (class "Default")
      (node (ref "P1") (pin "18") (pinfunction "18_18") (pintype "passive"))
    )
    (net (code "94") (name "unconnected-(P4-Pad6)") (class "Default")
      (node (ref "P4") (pin "6") (pinfunction "6_6") (pintype "passive"))
    )
    (net (code "95") (name "unconnected-(P4-Pad8)") (class "Default")
      (node (ref "P4") (pin "8") (pinfunction "8_8") (pintype "passive"))
    )
    (net (code "96") (name "unconnected-(P4-Pad10)") (class "Default")
      (node (ref "P4") (pin "10") (pinfunction "10_10") (pintype "passive"))
    )
    (net (code "97") (name "unconnected-(P4-Pad12)") (class "Default")
      (node (ref "P4") (pin "12") (pinfunction "12_12") (pintype "passive"))
    )
    (net (code "98") (name "unconnected-(P4-Pad14)") (class "Default")
      (node (ref "P4") (pin "14") (pinfunction "14_14") (pintype "passive"))
    )
    (net (code "99") (name "unconnected-(P4-Pad16)") (class "Default")
      (node (ref "P4") (pin "16") (pinfunction "16_16") (pintype "passive"))
    )
    (net (code "100") (name "unconnected-(P4-Pad18)") (class "Default")
      (node (ref "P4") (pin "18") (pinfunction "18_18") (pintype "passive"))
    )
    (net (code "101") (name "unconnected-(P4-Pad20)") (class "Default")
      (node (ref "P4") (pin "20") (pinfunction "20_20") (pintype "passive"))
    )
    (net (code "102") (name "unconnected-(P5-Pad17)") (class "Default")
      (node (ref "P5") (pin "17") (pinfunction "17_17") (pintype "passive"))
    )
    (net (code "103") (name "unconnected-(P5-Pad19)") (class "Default")
      (node (ref "P5") (pin "19") (pinfunction "19_19") (pintype "passive"))
    )
    (net (code "104") (name "unconnected-(P5-Pad20)") (class "Default")
      (node (ref "P5") (pin "20") (pinfunction "20_20") (pintype "passive"))
    )
    (net (code "105") (name "unconnected-(P10-Pad1)") (class "Default")
      (node (ref "P10") (pin "1") (pinfunction "1_1") (pintype "passive"))
    )
    (net (code "106") (name "unconnected-(U0-(A12)PC4-Pad57)") (class "Default")
      (node (ref "U0") (pin "57") (pinfunction "(A12)PC4_57") (pintype "passive"))
    )
    (net (code "107") (name "unconnected-(U0-(A13)PC5-Pad58)") (class "Default")
      (node (ref "U0") (pin "58") (pinfunction "(A13)PC5_58") (pintype "passive"))
    )
    (net (code "108") (name "unconnected-(U0-(A14)PC6-Pad59)") (class "Default")
      (node (ref "U0") (pin "59") (pinfunction "(A14)PC6_59") (pintype "passive"))
    )
    (net (code "109") (name "unconnected-(U0-(A15)PC7-Pad60)") (class "Default")
      (node (ref "U0") (pin "60") (pinfunction "(A15)PC7_60") (pintype "passive"))
    )
    (net (code "110") (name "unconnected-(U0-(AD0)PA0-Pad78)") (class "Default")
      (node (ref "U0") (pin "78") (pinfunction "(AD0)PA0_78") (pintype "passive"))
    )
    (net (code "111") (name "unconnected-(U0-(AD1)PA1-Pad77)") (class "Default")
      (node (ref "U0") (pin "77") (pinfunction "(AD1)PA1_77") (pintype "passive"))
    )
    (net (code "112") (name "unconnected-(U0-(AD2)PA2-Pad76)") (class "Default")
      (node (ref "U0") (pin "76") (pinfunction "(AD2)PA2_76") (pintype "passive"))
    )
    (net (code "113") (name "unconnected-(U0-(AD3)PA3-Pad75)") (class "Default")
      (node (ref "U0") (pin "75") (pinfunction "(AD3)PA3_75") (pintype "passive"))
    )
    (net (code "114") (name "unconnected-(U0-(AD4)PA4-Pad74)") (class "Default")
      (node (ref "U0") (pin "74") (pinfunction "(AD4)PA4_74") (pintype "passive"))
    )
    (net (code "115") (name "unconnected-(U0-(AD5)PA5-Pad73)") (class "Default")
      (node (ref "U0") (pin "73") (pinfunction "(AD5)PA5_73") (pintype "passive"))
    )
    (net (code "116") (name "unconnected-(U0-(AD6)PA6-Pad72)") (class "Default")
      (node (ref "U0") (pin "72") (pinfunction "(AD6)PA6_72") (pintype "passive"))
    )
    (net (code "117") (name "unconnected-(U0-(AD7)PA7-Pad71)") (class "Default")
      (node (ref "U0") (pin "71") (pinfunction "(AD7)PA7_71") (pintype "passive"))
    )
    (net (code "118") (name "unconnected-(U0-(ADC0)PF0-Pad97)") (class "Default")
      (node (ref "U0") (pin "97") (pinfunction "(ADC0)PF0_97") (pintype "passive"))
    )
    (net (code "119") (name "unconnected-(U0-(ADC1)PF1-Pad96)") (class "Default")
      (node (ref "U0") (pin "96") (pinfunction "(ADC1)PF1_96") (pintype "passive"))
    )
    (net (code "120") (name "unconnected-(U0-(ADC2)PF2-Pad95)") (class "Default")
      (node (ref "U0") (pin "95") (pinfunction "(ADC2)PF2_95") (pintype "passive"))
    )
    (net (code "121") (name "unconnected-(U0-(ADC3)PF3-Pad94)") (class "Default")
      (node (ref "U0") (pin "94") (pinfunction "(ADC3)PF3_94") (pintype "passive"))
    )
    (net (code "122") (name "unconnected-(U0-(ADC4{slash}TCK)PF4-Pad93)") (class "Default")
      (node (ref "U0") (pin "93") (pinfunction "(ADC4/TCK)PF4_93") (pintype "passive"))
    )
    (net (code "123") (name "unconnected-(U0-(ADC5{slash}TMS)PF5-Pad92)") (class "Default")
      (node (ref "U0") (pin "92") (pinfunction "(ADC5/TMS)PF5_92") (pintype "passive"))
    )
    (net (code "124") (name "unconnected-(U0-(ADC6{slash}TDO)PF6-Pad91)") (class "Default")
      (node (ref "U0") (pin "91") (pinfunction "(ADC6/TDO)PF6_91") (pintype "passive"))
    )
    (net (code "125") (name "unconnected-(U0-(ADC7{slash}TDI)PF7-Pad90)") (class "Default")
      (node (ref "U0") (pin "90") (pinfunction "(ADC7/TDI)PF7_90") (pintype "passive"))
    )
    (net (code "126") (name "unconnected-(U0-(ALE)PG2-Pad70)") (class "Default")
      (node (ref "U0") (pin "70") (pinfunction "(ALE)PG2_70") (pintype "passive"))
    )
    (net (code "127") (name "unconnected-(U0-(CLKO{slash}ICP3{slash}INT7)PE7-Pad9)") (class "Default")
      (node (ref "U0") (pin "9") (pinfunction "(CLKO/ICP3/INT7)PE7_9") (pintype "passive"))
    )
    (net (code "128") (name "unconnected-(U0-(ICP1)PD4-Pad47)") (class "Default")
      (node (ref "U0") (pin "47") (pinfunction "(ICP1)PD4_47") (pintype "passive"))
    )
    (net (code "129") (name "unconnected-(U0-(OC0A{slash}OC1C{slash}PCINT7)PB7-Pad26)") (class "Default")
      (node (ref "U0") (pin "26") (pinfunction "(OC0A/OC1C/PCINT7)PB7_26") (pintype "passive"))
    )
    (net (code "130") (name "unconnected-(U0-(OC0B)PG5-Pad1)") (class "Default")
      (node (ref "U0") (pin "1") (pinfunction "(OC0B)PG5_1") (pintype "passive"))
    )
    (net (code "131") (name "unconnected-(U0-(OC1A{slash}PCINT5)PB5-Pad24)") (class "Default")
      (node (ref "U0") (pin "24") (pinfunction "(OC1A/PCINT5)PB5_24") (pintype "passive"))
    )
    (net (code "132") (name "unconnected-(U0-(OC1B{slash}PCINT6)PB6-Pad25)") (class "Default")
      (node (ref "U0") (pin "25") (pinfunction "(OC1B/PCINT6)PB6_25") (pintype "passive"))
    )
    (net (code "133") (name "unconnected-(U0-(OC2A{slash}PCINT4)PB4-Pad23)") (class "Default")
      (node (ref "U0") (pin "23") (pinfunction "(OC2A/PCINT4)PB4_23") (pintype "passive"))
    )
    (net (code "134") (name "unconnected-(U0-(OC3A{slash}AIN1)PE3-Pad5)") (class "Default")
      (node (ref "U0") (pin "5") (pinfunction "(OC3A/AIN1)PE3_5") (pintype "passive"))
    )
    (net (code "135") (name "unconnected-(U0-(OC3B{slash}INT4)PE4-Pad6)") (class "Default")
      (node (ref "U0") (pin "6") (pinfunction "(OC3B/INT4)PE4_6") (pintype "passive"))
    )
    (net (code "136") (name "unconnected-(U0-(OC3C{slash}INT5)PE5-Pad7)") (class "Default")
      (node (ref "U0") (pin "7") (pinfunction "(OC3C/INT5)PE5_7") (pintype "passive"))
    )
    (net (code "137") (name "unconnected-(U0-(RD)PG1-Pad52)") (class "Default")
      (node (ref "U0") (pin "52") (pinfunction "(RD)PG1_52") (pintype "passive"))
    )
    (net (code "138") (name "unconnected-(U0-(SS{slash}PCINT0)PB0-Pad19)") (class "Default")
      (node (ref "U0") (pin "19") (pinfunction "(SS/PCINT0)PB0_19") (pintype "passive"))
    )
    (net (code "139") (name "unconnected-(U0-(T0)PD7-Pad50)") (class "Default")
      (node (ref "U0") (pin "50") (pinfunction "(T0)PD7_50") (pintype "passive"))
    )
    (net (code "140") (name "unconnected-(U0-(T1)PD6-Pad49)") (class "Default")
      (node (ref "U0") (pin "49") (pinfunction "(T1)PD6_49") (pintype "passive"))
    )
    (net (code "141") (name "unconnected-(U0-(T3{slash}INT6)PE6-Pad8)") (class "Default")
      (node (ref "U0") (pin "8") (pinfunction "(T3/INT6)PE6_8") (pintype "passive"))
    )
    (net (code "142") (name "unconnected-(U0-(TOSC1)PG4-Pad29)") (class "Default")
      (node (ref "U0") (pin "29") (pinfunction "(TOSC1)PG4_29") (pintype "passive"))
    )
    (net (code "143") (name "unconnected-(U0-(TOSC2)PG3-Pad28)") (class "Default")
      (node (ref "U0") (pin "28") (pinfunction "(TOSC2)PG3_28") (pintype "passive"))
    )
    (net (code "144") (name "unconnected-(U0-(WR)PG0-Pad51)") (class "Default")
      (node (ref "U0") (pin "51") (pinfunction "(WR)PG0_51") (pintype "passive"))
    )
    (net (code "145") (name "unconnected-(U0-(XCK0{slash}AIN0)PE2-Pad4)") (class "Default")
      (node (ref "U0") (pin "4") (pinfunction "(XCK0/AIN0)PE2_4") (pintype "passive"))
    )
    (net (code "146") (name "unconnected-(U0-(XCK1)PD5-Pad48)") (class "Default")
      (node (ref "U0") (pin "48") (pinfunction "(XCK1)PD5_48") (pintype "passive"))
    )
    (net (code "147") (name "unconnected-(U0-PH2(XCK2)-Pad14)") (class "Default")
      (node (ref "U0") (pin "14") (pinfunction "PH2(XCK2)_14") (pintype "passive"))
    )
    (net (code "148") (name "unconnected-(U0-PH3(OC4A)-Pad15)") (class "Default")
      (node (ref "U0") (pin "15") (pinfunction "PH3(OC4A)_15") (pintype "passive"))
    )
    (net (code "149") (name "unconnected-(U0-PH4(OC4B)-Pad16)") (class "Default")
      (node (ref "U0") (pin "16") (pinfunction "PH4(OC4B)_16") (pintype "passive"))
    )
    (net (code "150") (name "unconnected-(U0-PH5(OC4C)-Pad17)") (class "Default")
      (node (ref "U0") (pin "17") (pinfunction "PH5(OC4C)_17") (pintype "passive"))
    )
    (net (code "151") (name "unconnected-(U0-PH6(OC2B)-Pad18)") (class "Default")
      (node (ref "U0") (pin "18") (pinfunction "PH6(OC2B)_18") (pintype "passive"))
    )
    (net (code "152") (name "unconnected-(U0-PH7(T4)-Pad27)") (class "Default")
      (node (ref "U0") (pin "27") (pinfunction "PH7(T4)_27") (pintype "passive"))
    )
    (net (code "153") (name "unconnected-(U0-PJ2(XCK3{slash}PCINT11)-Pad65)") (class "Default")
      (node (ref "U0") (pin "65") (pinfunction "PJ2(XCK3/PCINT11)_65") (pintype "passive"))
    )
    (net (code "154") (name "unconnected-(U0-PJ3(PCINT12)-Pad66)") (class "Default")
      (node (ref "U0") (pin "66") (pinfunction "PJ3(PCINT12)_66") (pintype "passive"))
    )
    (net (code "155") (name "unconnected-(U0-PJ4(PCINT13)-Pad67)") (class "Default")
      (node (ref "U0") (pin "67") (pinfunction "PJ4(PCINT13)_67") (pintype "passive"))
    )
    (net (code "156") (name "unconnected-(U0-PJ5(PCINT14)-Pad68)") (class "Default")
      (node (ref "U0") (pin "68") (pinfunction "PJ5(PCINT14)_68") (pintype "passive"))
    )
    (net (code "157") (name "unconnected-(U0-PJ6(PCINT15)-Pad69)") (class "Default")
      (node (ref "U0") (pin "69") (pinfunction "PJ6(PCINT15)_69") (pintype "passive"))
    )
    (net (code "158") (name "unconnected-(U0-PJ7-Pad79)") (class "Default")
      (node (ref "U0") (pin "79") (pinfunction "PJ7_79") (pintype "passive"))
    )
    (net (code "159") (name "unconnected-(U0-PK0(ADC8{slash}PCINT16)-Pad89)") (class "Default")
      (node (ref "U0") (pin "89") (pinfunction "PK0(ADC8/PCINT16)_89") (pintype "passive"))
    )
    (net (code "160") (name "unconnected-(U0-PK1(ADC9{slash}PCINT17)-Pad88)") (class "Default")
      (node (ref "U0") (pin "88") (pinfunction "PK1(ADC9/PCINT17)_88") (pintype "passive"))
    )
    (net (code "161") (name "unconnected-(U0-PK2(ADC10{slash}PCINT18)-Pad87)") (class "Default")
      (node (ref "U0") (pin "87") (pinfunction "PK2(ADC10/PCINT18)_87") (pintype "passive"))
    )
    (net (code "162") (name "unconnected-(U0-PK3(ADC11{slash}PCINT19)-Pad86)") (class "Default")
      (node (ref "U0") (pin "86") (pinfunction "PK3(ADC11/PCINT19)_86") (pintype "passive"))
    )
    (net (code "163") (name "unconnected-(U0-PK4(ADC12{slash}PCINT20)-Pad85)") (class "Default")
      (node (ref "U0") (pin "85") (pinfunction "PK4(ADC12/PCINT20)_85") (pintype "passive"))
    )
    (net (code "164") (name "unconnected-(U0-PK5(ADC13{slash}PCINT21)-Pad84)") (class "Default")
      (node (ref "U0") (pin "84") (pinfunction "PK5(ADC13/PCINT21)_84") (pintype "passive"))
    )
    (net (code "165") (name "unconnected-(U0-PK6(ADC14{slash}PCINT22)-Pad83)") (class "Default")
      (node (ref "U0") (pin "83") (pinfunction "PK6(ADC14/PCINT22)_83") (pintype "passive"))
    )
    (net (code "166") (name "unconnected-(U0-PK7(ADC15{slash}PCINT23)-Pad82)") (class "Default")
      (node (ref "U0") (pin "82") (pinfunction "PK7(ADC15/PCINT23)_82") (pintype "passive"))
    )
    (net (code "167") (name "unconnected-(U0-PL1(ICP5)-Pad36)") (class "Default")
      (node (ref "U0") (pin "36") (pinfunction "PL1(ICP5)_36") (pintype "passive"))
    )
    (net (code "168") (name "unconnected-(U0-PL2(T5)-Pad37)") (class "Default")
      (node (ref "U0") (pin "37") (pinfunction "PL2(T5)_37") (pintype "passive"))
    )
    (net (code "169") (name "unconnected-(U0-PL3(OC5A)-Pad38)") (class "Default")
      (node (ref "U0") (pin "38") (pinfunction "PL3(OC5A)_38") (pintype "passive"))
    )
    (net (code "170") (name "unconnected-(U0-PL4(OC5B)-Pad39)") (class "Default")
      (node (ref "U0") (pin "39") (pinfunction "PL4(OC5B)_39") (pintype "passive"))
    )
    (net (code "171") (name "unconnected-(U0-PL5(OC5C)-Pad40)") (class "Default")
      (node (ref "U0") (pin "40") (pinfunction "PL5(OC5C)_40") (pintype "passive"))
    )
    (net (code "172") (name "unconnected-(U0-PL6-Pad41)") (class "Default")
      (node (ref "U0") (pin "41") (pinfunction "PL6_41") (pintype "passive"))
    )
    (net (code "173") (name "unconnected-(U0-PL7-Pad42)") (class "Default")
      (node (ref "U0") (pin "42") (pinfunction "PL7_42") (pintype "passive"))
    )
  )
)
